# InternetButtonBuzzer.net
KiCad netlist of a schematic drawn in EAGLE
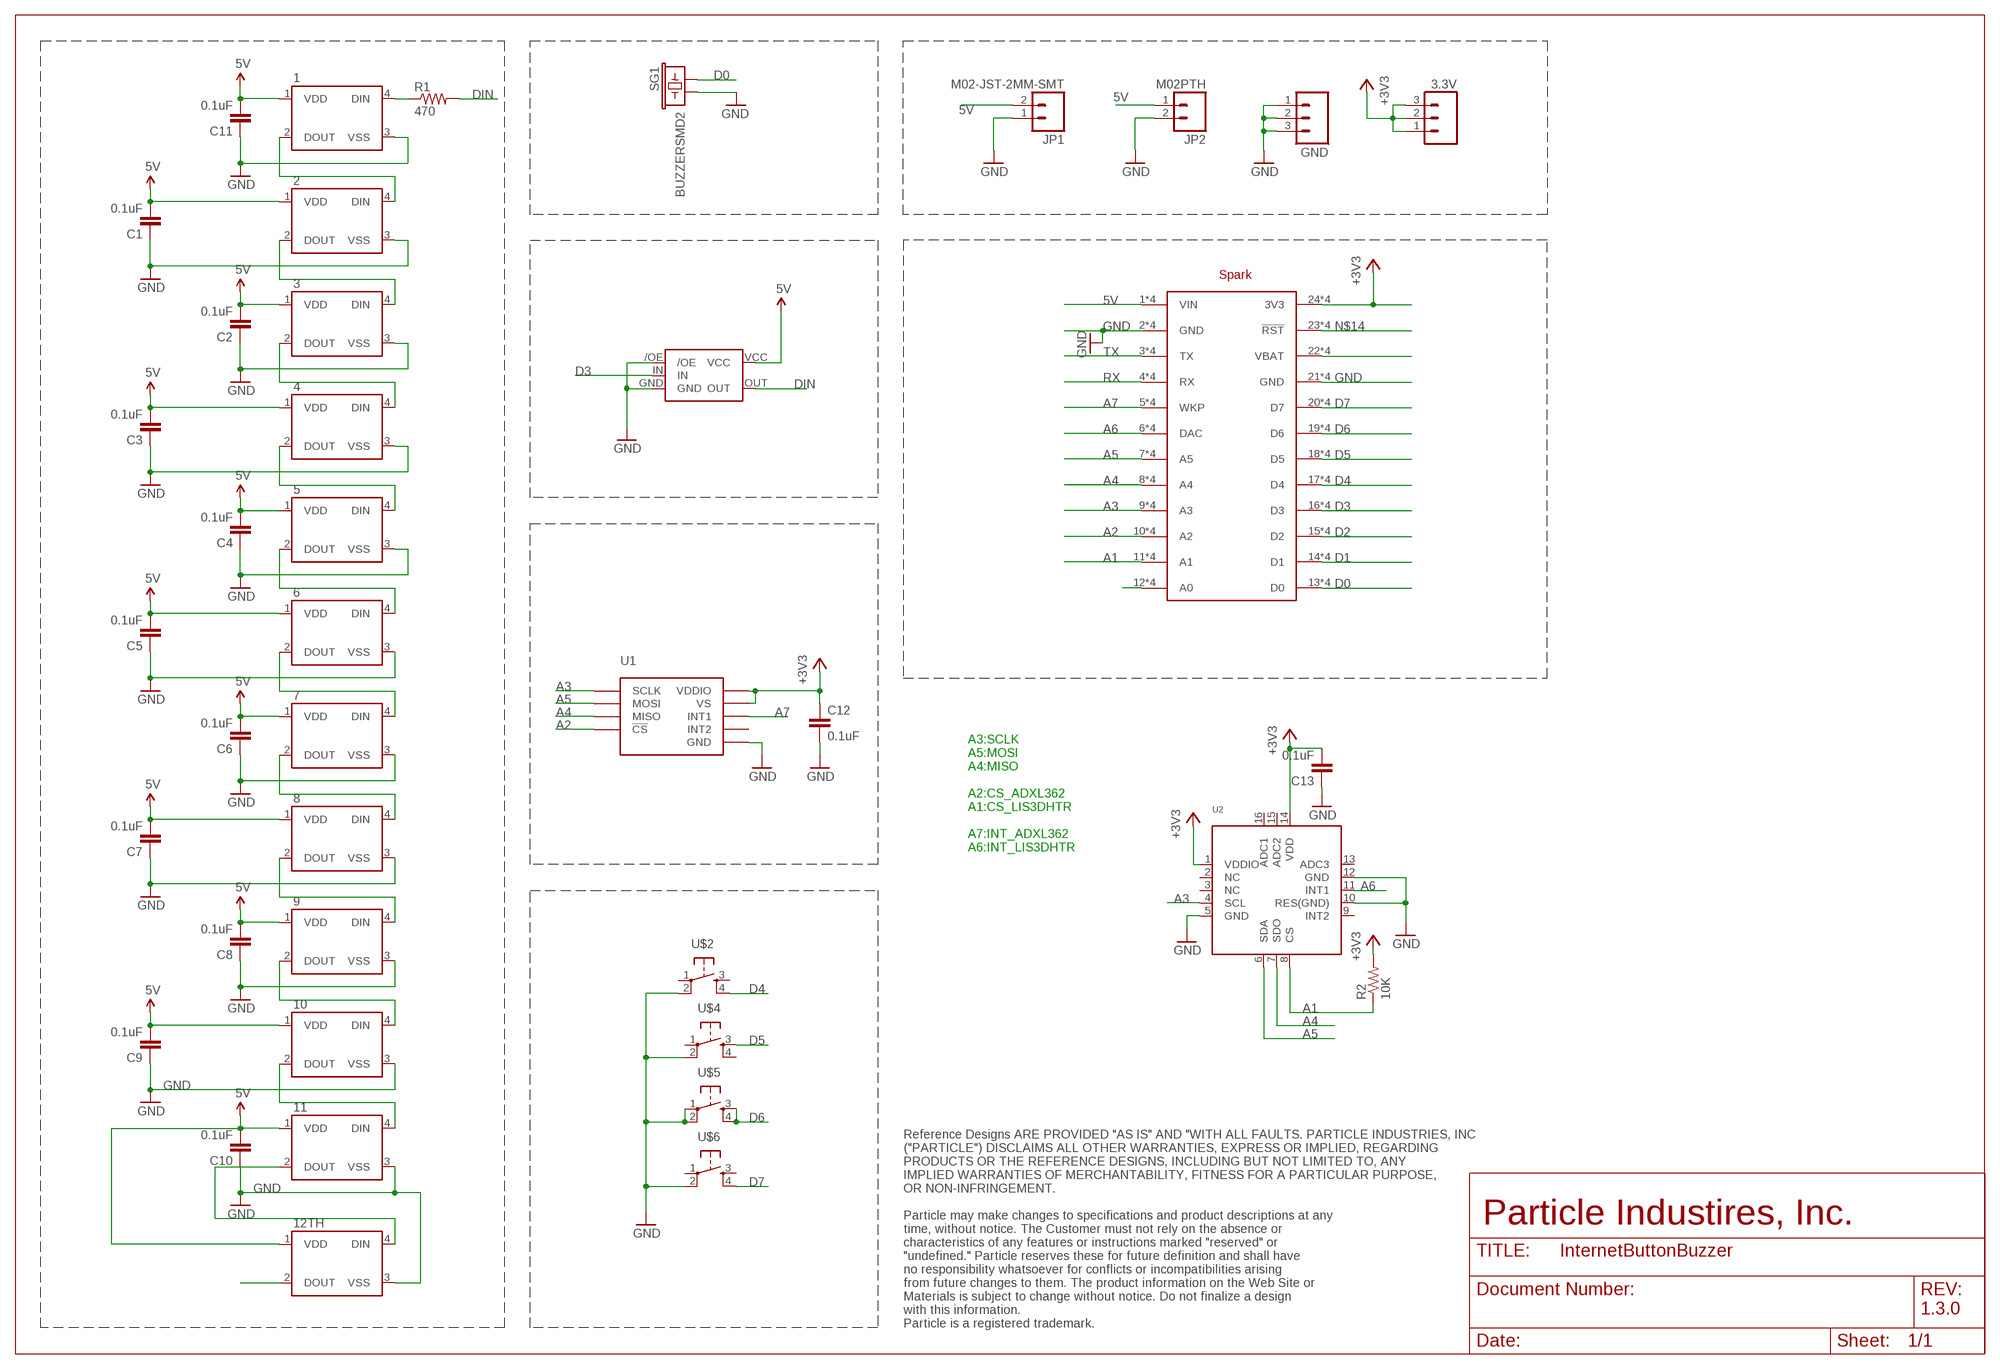
[diagram p0: schematic, sheet 1]

(export (version "E")
  (design (tool "Eeschema 10.0.6"))
  (components
    (comp (ref "1")
      (value "WS2812B")
      (footprint "eagle-import:WS2812B")
      (libsource (lib "eagle-import") (part "SparkFun-LED_WS2812B"))
    )
    (comp (ref "2")
      (value "WS2812B")
      (footprint "eagle-import:WS2812B")
      (libsource (lib "eagle-import") (part "SparkFun-LED_WS2812B"))
    )
    (comp (ref "3")
      (value "WS2812B")
      (footprint "eagle-import:WS2812B")
      (libsource (lib "eagle-import") (part "SparkFun-LED_WS2812B"))
    )
    (comp (ref "3.3V")
      (value "M03LOCK_NO_SILK")
      (footprint "eagle-import:1X03_LOCK_NO_SILK")
      (libsource (lib "eagle-import") (part "M03LOCK_NO_SILK"))
    )
    (comp (ref "4")
      (value "WS2812B")
      (footprint "eagle-import:WS2812B")
      (libsource (lib "eagle-import") (part "SparkFun-LED_WS2812B"))
    )
    (comp (ref "5")
      (value "WS2812B")
      (footprint "eagle-import:WS2812B")
      (libsource (lib "eagle-import") (part "SparkFun-LED_WS2812B"))
    )
    (comp (ref "6")
      (value "WS2812B")
      (footprint "eagle-import:WS2812B")
      (libsource (lib "eagle-import") (part "SparkFun-LED_WS2812B"))
    )
    (comp (ref "7")
      (value "WS2812B")
      (footprint "eagle-import:WS2812B")
      (libsource (lib "eagle-import") (part "SparkFun-LED_WS2812B"))
    )
    (comp (ref "8")
      (value "WS2812B")
      (footprint "eagle-import:WS2812B")
      (libsource (lib "eagle-import") (part "SparkFun-LED_WS2812B"))
    )
    (comp (ref "9")
      (value "WS2812B")
      (footprint "eagle-import:WS2812B")
      (libsource (lib "eagle-import") (part "SparkFun-LED_WS2812B"))
    )
    (comp (ref "10")
      (value "WS2812B")
      (footprint "eagle-import:WS2812B")
      (libsource (lib "eagle-import") (part "SparkFun-LED_WS2812B"))
    )
    (comp (ref "11")
      (value "WS2812B")
      (footprint "eagle-import:WS2812B")
      (libsource (lib "eagle-import") (part "SparkFun-LED_WS2812B"))
    )
    (comp (ref "12TH")
      (value "WS2812B")
      (footprint "eagle-import:NOCREAM_WS2812B")
      (libsource (lib "eagle-import") (part "WS2812B"))
    )
    (comp (ref "C1")
      (value "0.1uF")
      (footprint "eagle-import:0603-CAP")
      (libsource (lib "eagle-import") (part "15PF-50V-5%(0603)"))
    )
    (comp (ref "C2")
      (value "0.1uF")
      (footprint "eagle-import:0603-CAP")
      (libsource (lib "eagle-import") (part "15PF-50V-5%(0603)"))
    )
    (comp (ref "C3")
      (value "0.1uF")
      (footprint "eagle-import:0603-CAP")
      (libsource (lib "eagle-import") (part "15PF-50V-5%(0603)"))
    )
    (comp (ref "C4")
      (value "0.1uF")
      (footprint "eagle-import:0603-CAP")
      (libsource (lib "eagle-import") (part "15PF-50V-5%(0603)"))
    )
    (comp (ref "C5")
      (value "0.1uF")
      (footprint "eagle-import:0603-CAP")
      (libsource (lib "eagle-import") (part "15PF-50V-5%(0603)"))
    )
    (comp (ref "C6")
      (value "0.1uF")
      (footprint "eagle-import:0603-CAP")
      (libsource (lib "eagle-import") (part "15PF-50V-5%(0603)"))
    )
    (comp (ref "C7")
      (value "0.1uF")
      (footprint "eagle-import:0603-CAP")
      (libsource (lib "eagle-import") (part "15PF-50V-5%(0603)"))
    )
    (comp (ref "C8")
      (value "0.1uF")
      (footprint "eagle-import:0603-CAP")
      (libsource (lib "eagle-import") (part "15PF-50V-5%(0603)"))
    )
    (comp (ref "C9")
      (value "0.1uF")
      (footprint "eagle-import:0603-CAP")
      (libsource (lib "eagle-import") (part "15PF-50V-5%(0603)"))
    )
    (comp (ref "C10")
      (value "0.1uF")
      (footprint "eagle-import:0603-CAP")
      (libsource (lib "eagle-import") (part "15PF-50V-5%(0603)"))
    )
    (comp (ref "C11")
      (value "0.1uF")
      (footprint "eagle-import:0603-CAP")
      (libsource (lib "eagle-import") (part "15PF-50V-5%(0603)"))
    )
    (comp (ref "C12")
      (value "0.1uF")
      (footprint "eagle-import:0603-CAP")
      (libsource (lib "eagle-import") (part "CAP0603-CAP"))
    )
    (comp (ref "C13")
      (value "0.1uF")
      (footprint "eagle-import:0603-CAP")
      (libsource (lib "eagle-import") (part "CAP0603-CAP"))
    )
    (comp (ref "GND")
      (value "M03LOCK_NO_SILK")
      (footprint "eagle-import:1X03_LOCK_NO_SILK")
      (libsource (lib "eagle-import") (part "M03LOCK_NO_SILK"))
    )
    (comp (ref "JP1")
      (value "M02-JST-2MM-SMT")
      (footprint "eagle-import:JST-2-SMD")
      (libsource (lib "eagle-import") (part "M02-JST-2MM-SMT"))
    )
    (comp (ref "JP2")
      (value "M02PTH")
      (footprint "eagle-import:1X02")
      (libsource (lib "eagle-import") (part "M02PTH"))
    )
    (comp (ref "R1")
      (value "470")
      (footprint "eagle-import:0603-RES")
      (libsource (lib "eagle-import") (part "470OHM1/10W1%(0603)"))
    )
    (comp (ref "R2")
      (value "10K")
      (footprint "eagle-import:0603-RES")
      (libsource (lib "eagle-import") (part "470OHM1/10W1%(0603)"))
    )
    (comp (ref "SG1")
      (value "BUZZERSMD2")
      (footprint "eagle-import:BUZZER-CCV")
      (libsource (lib "eagle-import") (part "BUZZERSMD2"))
    )
    (comp (ref "U$2")
      (value "12MM_TACTILE_SWITCH")
      (footprint "eagle-import:12MM_TACTILE_SWITCH")
      (libsource (lib "eagle-import") (part "12MM_TACTILE_SWITCH"))
    )
    (comp (ref "U$3")
      (value "SPARK_LOGO_WITH_PLANE")
      (footprint "eagle-import:SPARK_LOGO_PLUS_PLANE")
      (libsource (lib "eagle-import") (part "SPARK_LOGO_WITH_PLANE"))
    )
    (comp (ref "U$4")
      (value "12MM_TACTILE_SWITCH")
      (footprint "eagle-import:12MM_TACTILE_SWITCH")
      (libsource (lib "eagle-import") (part "12MM_TACTILE_SWITCH"))
    )
    (comp (ref "U$5")
      (value "12MM_TACTILE_SWITCH")
      (footprint "eagle-import:12MM_TACTILE_SWITCH")
      (libsource (lib "eagle-import") (part "12MM_TACTILE_SWITCH"))
    )
    (comp (ref "U$6")
      (value "12MM_TACTILE_SWITCH")
      (footprint "eagle-import:12MM_TACTILE_SWITCH")
      (libsource (lib "eagle-import") (part "12MM_TACTILE_SWITCH"))
    )
    (comp (ref "U$7")
      (value "SPARK_COREDUAL_HEADER")
      (footprint "eagle-import:SPARK_CORE_DUAL_HEADER")
      (libsource (lib "eagle-import") (part "SPARK_COREDUAL_HEADER"))
    )
    (comp (ref "U$8")
      (value "NL17SZ125SOT553")
      (footprint "eagle-import:SOT-553")
      (libsource (lib "eagle-import") (part "NL17SZ125SOT553"))
    )
    (comp (ref "U1")
      (value "ADXL362ADXL362-1:1")
      (footprint "eagle-import:ADXL362-1_1")
      (libsource (lib "eagle-import") (part "ADXL362ADXL362-1{colon}1"))
    )
    (comp (ref "U2")
      (value "ACCEL_LIS3DHTR")
      (footprint "eagle-import:LGA16_3X3MM")
      (libsource (lib "eagle-import") (part "ACCEL_LIS3DHTR"))
    )
  )
  (nets
    (net (code "1") (name "+3V3") (class "Default")
      (node (ref "3.3V") (pin "1") (pinfunction "1_1") (pintype "passive"))
      (node (ref "3.3V") (pin "2") (pinfunction "2_2") (pintype "passive"))
      (node (ref "3.3V") (pin "3") (pinfunction "3_3") (pintype "passive"))
      (node (ref "C12") (pin "1") (pinfunction "1_1") (pintype "passive"))
      (node (ref "C13") (pin "2") (pinfunction "2_2") (pintype "passive"))
      (node (ref "R2") (pin "2") (pinfunction "2_2") (pintype "passive"))
      (node (ref "U$7") (pin "24") (pinfunction "3V3_24") (pintype "power_in"))
      (node (ref "U$7") (pin "24B") (pinfunction "3V3_24B") (pintype "power_in"))
      (node (ref "U$7") (pin "@24") (pinfunction "3V3_@24") (pintype "power_in"))
      (node (ref "U$7") (pin "@24B") (pinfunction "3V3_@24B") (pintype "power_in"))
      (node (ref "U1") (pin "P$1") (pinfunction "VDDIO_P$1") (pintype "bidirectional"))
      (node (ref "U1") (pin "P$14") (pinfunction "VS_P$14") (pintype "bidirectional"))
      (node (ref "U2") (pin "1") (pinfunction "VDDIO_1") (pintype "power_in"))
      (node (ref "U2") (pin "14") (pinfunction "VDD_14") (pintype "power_in"))
    )
    (net (code "2") (name "/A1") (class "Default")
      (node (ref "R2") (pin "1") (pinfunction "1_1") (pintype "passive"))
      (node (ref "U$7") (pin "11") (pinfunction "A1_11") (pintype "bidirectional"))
      (node (ref "U$7") (pin "11B") (pinfunction "A1_11B") (pintype "bidirectional"))
      (node (ref "U$7") (pin "@11") (pinfunction "A1_@11") (pintype "bidirectional"))
      (node (ref "U$7") (pin "@11B") (pinfunction "A1_@11B") (pintype "bidirectional"))
      (node (ref "U2") (pin "8") (pinfunction "CS_8") (pintype "input"))
    )
    (net (code "3") (name "/A2") (class "Default")
      (node (ref "U$7") (pin "10") (pinfunction "A2_10") (pintype "bidirectional"))
      (node (ref "U$7") (pin "10B") (pinfunction "A2_10B") (pintype "bidirectional"))
      (node (ref "U$7") (pin "@10") (pinfunction "A2_@10") (pintype "bidirectional"))
      (node (ref "U$7") (pin "@10B") (pinfunction "A2_@10B") (pintype "bidirectional"))
      (node (ref "U1") (pin "P$8") (pinfunction "~{CS}_P$8") (pintype "bidirectional"))
    )
    (net (code "4") (name "/A3") (class "Default")
      (node (ref "U$7") (pin "9") (pinfunction "A3_9") (pintype "bidirectional"))
      (node (ref "U$7") (pin "9B") (pinfunction "A3_9B") (pintype "bidirectional"))
      (node (ref "U$7") (pin "@9") (pinfunction "A3_@9") (pintype "bidirectional"))
      (node (ref "U$7") (pin "@9B") (pinfunction "A3_@9B") (pintype "bidirectional"))
      (node (ref "U1") (pin "P$4") (pinfunction "SCLK_P$4") (pintype "bidirectional"))
      (node (ref "U2") (pin "4") (pinfunction "SCL_4") (pintype "bidirectional"))
    )
    (net (code "5") (name "/A4") (class "Default")
      (node (ref "U$7") (pin "8") (pinfunction "A4_8") (pintype "bidirectional"))
      (node (ref "U$7") (pin "8B") (pinfunction "A4_8B") (pintype "bidirectional"))
      (node (ref "U$7") (pin "@8") (pinfunction "A4_@8") (pintype "bidirectional"))
      (node (ref "U$7") (pin "@8B") (pinfunction "A4_@8B") (pintype "bidirectional"))
      (node (ref "U1") (pin "P$7") (pinfunction "MISO_P$7") (pintype "bidirectional"))
      (node (ref "U2") (pin "7") (pinfunction "SDO_7") (pintype "bidirectional"))
    )
    (net (code "6") (name "/A5") (class "Default")
      (node (ref "U$7") (pin "7") (pinfunction "A5_7") (pintype "bidirectional"))
      (node (ref "U$7") (pin "7B") (pinfunction "A5_7B") (pintype "bidirectional"))
      (node (ref "U$7") (pin "@7") (pinfunction "A5_@7") (pintype "bidirectional"))
      (node (ref "U$7") (pin "@7B") (pinfunction "A5_@7B") (pintype "bidirectional"))
      (node (ref "U1") (pin "P$6") (pinfunction "MOSI_P$6") (pintype "bidirectional"))
      (node (ref "U2") (pin "6") (pinfunction "SDA_6") (pintype "bidirectional"))
    )
    (net (code "7") (name "/A6") (class "Default")
      (node (ref "U$7") (pin "6") (pinfunction "DAC_6") (pintype "bidirectional"))
      (node (ref "U$7") (pin "6B") (pinfunction "DAC_6B") (pintype "bidirectional"))
      (node (ref "U$7") (pin "@6") (pinfunction "DAC_@6") (pintype "bidirectional"))
      (node (ref "U$7") (pin "@6B") (pinfunction "DAC_@6B") (pintype "bidirectional"))
      (node (ref "U2") (pin "11") (pinfunction "INT1_11") (pintype "output"))
    )
    (net (code "8") (name "/A7") (class "Default")
      (node (ref "U$7") (pin "5") (pinfunction "WKP_5") (pintype "bidirectional"))
      (node (ref "U$7") (pin "5B") (pinfunction "WKP_5B") (pintype "bidirectional"))
      (node (ref "U$7") (pin "@5") (pinfunction "WKP_@5") (pintype "bidirectional"))
      (node (ref "U$7") (pin "@5B") (pinfunction "WKP_@5B") (pintype "bidirectional"))
      (node (ref "U1") (pin "P$11") (pinfunction "INT1_P$11") (pintype "bidirectional"))
    )
    (net (code "9") (name "/D0") (class "Default")
      (node (ref "SG1") (pin "+") (pinfunction "1_+") (pintype "passive"))
      (node (ref "U$7") (pin "13") (pinfunction "D0_13") (pintype "bidirectional"))
      (node (ref "U$7") (pin "13B") (pinfunction "D0_13B") (pintype "bidirectional"))
      (node (ref "U$7") (pin "@13") (pinfunction "D0_@13") (pintype "bidirectional"))
      (node (ref "U$7") (pin "@13B") (pinfunction "D0_@13B") (pintype "bidirectional"))
    )
    (net (code "10") (name "/D1") (class "Default")
      (node (ref "U$7") (pin "14") (pinfunction "D1_14") (pintype "bidirectional"))
      (node (ref "U$7") (pin "14B") (pinfunction "D1_14B") (pintype "bidirectional"))
      (node (ref "U$7") (pin "@14") (pinfunction "D1_@14") (pintype "bidirectional"))
      (node (ref "U$7") (pin "@14B") (pinfunction "D1_@14B") (pintype "bidirectional"))
    )
    (net (code "11") (name "/D2") (class "Default")
      (node (ref "U$7") (pin "15") (pinfunction "D2_15") (pintype "bidirectional"))
      (node (ref "U$7") (pin "15B") (pinfunction "D2_15B") (pintype "bidirectional"))
      (node (ref "U$7") (pin "@15") (pinfunction "D2_@15") (pintype "bidirectional"))
      (node (ref "U$7") (pin "@15B") (pinfunction "D2_@15B") (pintype "bidirectional"))
    )
    (net (code "12") (name "/D3") (class "Default")
      (node (ref "U$7") (pin "16") (pinfunction "D3_16") (pintype "bidirectional"))
      (node (ref "U$7") (pin "16B") (pinfunction "D3_16B") (pintype "bidirectional"))
      (node (ref "U$7") (pin "@16") (pinfunction "D3_@16") (pintype "bidirectional"))
      (node (ref "U$7") (pin "@16B") (pinfunction "D3_@16B") (pintype "bidirectional"))
      (node (ref "U$8") (pin "IN") (pinfunction "IN_IN") (pintype "bidirectional"))
    )
    (net (code "13") (name "/D4") (class "Default")
      (node (ref "U$2") (pin "4") (pinfunction "4_4") (pintype "passive"))
      (node (ref "U$7") (pin "17") (pinfunction "D4_17") (pintype "bidirectional"))
      (node (ref "U$7") (pin "17B") (pinfunction "D4_17B") (pintype "bidirectional"))
      (node (ref "U$7") (pin "@17") (pinfunction "D4_@17") (pintype "bidirectional"))
      (node (ref "U$7") (pin "@17B") (pinfunction "D4_@17B") (pintype "bidirectional"))
    )
    (net (code "14") (name "/D5") (class "Default")
      (node (ref "U$4") (pin "3") (pinfunction "3_3") (pintype "passive"))
      (node (ref "U$7") (pin "18") (pinfunction "D5_18") (pintype "bidirectional"))
      (node (ref "U$7") (pin "18B") (pinfunction "D5_18B") (pintype "bidirectional"))
      (node (ref "U$7") (pin "@18") (pinfunction "D5_@18") (pintype "bidirectional"))
      (node (ref "U$7") (pin "@18B") (pinfunction "D5_@18B") (pintype "bidirectional"))
    )
    (net (code "15") (name "/D6") (class "Default")
      (node (ref "U$5") (pin "3") (pinfunction "3_3") (pintype "passive"))
      (node (ref "U$5") (pin "4") (pinfunction "4_4") (pintype "passive"))
      (node (ref "U$7") (pin "19") (pinfunction "D6_19") (pintype "bidirectional"))
      (node (ref "U$7") (pin "19B") (pinfunction "D6_19B") (pintype "bidirectional"))
      (node (ref "U$7") (pin "@19") (pinfunction "D6_@19") (pintype "bidirectional"))
      (node (ref "U$7") (pin "@19B") (pinfunction "D6_@19B") (pintype "bidirectional"))
    )
    (net (code "16") (name "/D7") (class "Default")
      (node (ref "U$6") (pin "4") (pinfunction "4_4") (pintype "passive"))
      (node (ref "U$7") (pin "20") (pinfunction "D7_20") (pintype "bidirectional"))
      (node (ref "U$7") (pin "20B") (pinfunction "D7_20B") (pintype "bidirectional"))
      (node (ref "U$7") (pin "@20") (pinfunction "D7_@20") (pintype "bidirectional"))
      (node (ref "U$7") (pin "@20B") (pinfunction "D7_@20B") (pintype "bidirectional"))
    )
    (net (code "17") (name "/DIN") (class "Default")
      (node (ref "R1") (pin "2") (pinfunction "2_2") (pintype "passive"))
      (node (ref "U$8") (pin "OUT") (pinfunction "OUT_OUT") (pintype "bidirectional"))
    )
    (net (code "18") (name "/N$14") (class "Default")
      (node (ref "U$7") (pin "23") (pinfunction "~{RST}_23") (pintype "bidirectional"))
      (node (ref "U$7") (pin "23B") (pinfunction "~{RST}_23B") (pintype "bidirectional"))
      (node (ref "U$7") (pin "@23") (pinfunction "~{RST}_@23") (pintype "bidirectional"))
      (node (ref "U$7") (pin "@23B") (pinfunction "~{RST}_@23B") (pintype "bidirectional"))
    )
    (net (code "19") (name "/RX") (class "Default")
      (node (ref "U$7") (pin "4") (pinfunction "RX_4") (pintype "bidirectional"))
      (node (ref "U$7") (pin "4B") (pinfunction "RX_4B") (pintype "bidirectional"))
      (node (ref "U$7") (pin "@4") (pinfunction "RX_@4") (pintype "bidirectional"))
      (node (ref "U$7") (pin "@4B") (pinfunction "RX_@4B") (pintype "bidirectional"))
    )
    (net (code "20") (name "/TX") (class "Default")
      (node (ref "U$7") (pin "3") (pinfunction "TX_3") (pintype "bidirectional"))
      (node (ref "U$7") (pin "3B") (pinfunction "TX_3B") (pintype "bidirectional"))
      (node (ref "U$7") (pin "@3") (pinfunction "TX_@3") (pintype "bidirectional"))
      (node (ref "U$7") (pin "@3B") (pinfunction "TX_@3B") (pintype "bidirectional"))
    )
    (net (code "21") (name "5V") (class "Default")
      (node (ref "1") (pin "1") (pinfunction "VDD_1") (pintype "power_in"))
      (node (ref "10") (pin "1") (pinfunction "VDD_1") (pintype "power_in"))
      (node (ref "11") (pin "1") (pinfunction "VDD_1") (pintype "power_in"))
      (node (ref "12TH") (pin "1") (pinfunction "VDD_1") (pintype "power_in"))
      (node (ref "2") (pin "1") (pinfunction "VDD_1") (pintype "power_in"))
      (node (ref "3") (pin "1") (pinfunction "VDD_1") (pintype "power_in"))
      (node (ref "4") (pin "1") (pinfunction "VDD_1") (pintype "power_in"))
      (node (ref "5") (pin "1") (pinfunction "VDD_1") (pintype "power_in"))
      (node (ref "6") (pin "1") (pinfunction "VDD_1") (pintype "power_in"))
      (node (ref "7") (pin "1") (pinfunction "VDD_1") (pintype "power_in"))
      (node (ref "8") (pin "1") (pinfunction "VDD_1") (pintype "power_in"))
      (node (ref "9") (pin "1") (pinfunction "VDD_1") (pintype "power_in"))
      (node (ref "C1") (pin "2") (pinfunction "2_2") (pintype "passive"))
      (node (ref "C10") (pin "2") (pinfunction "2_2") (pintype "passive"))
      (node (ref "C11") (pin "2") (pinfunction "2_2") (pintype "passive"))
      (node (ref "C2") (pin "2") (pinfunction "2_2") (pintype "passive"))
      (node (ref "C3") (pin "2") (pinfunction "2_2") (pintype "passive"))
      (node (ref "C4") (pin "2") (pinfunction "2_2") (pintype "passive"))
      (node (ref "C5") (pin "2") (pinfunction "2_2") (pintype "passive"))
      (node (ref "C6") (pin "2") (pinfunction "2_2") (pintype "passive"))
      (node (ref "C7") (pin "2") (pinfunction "2_2") (pintype "passive"))
      (node (ref "C8") (pin "2") (pinfunction "2_2") (pintype "passive"))
      (node (ref "C9") (pin "2") (pinfunction "2_2") (pintype "passive"))
      (node (ref "JP1") (pin "2") (pinfunction "1_2") (pintype "passive"))
      (node (ref "JP2") (pin "1") (pinfunction "1_1") (pintype "passive"))
      (node (ref "U$7") (pin "1") (pinfunction "VIN_1") (pintype "power_in"))
      (node (ref "U$7") (pin "1B") (pinfunction "VIN_1B") (pintype "power_in"))
      (node (ref "U$7") (pin "@1") (pinfunction "VIN_@1") (pintype "power_in"))
      (node (ref "U$7") (pin "@1B") (pinfunction "VIN_@1B") (pintype "power_in"))
      (node (ref "U$8") (pin "VCC") (pinfunction "VCC_VCC") (pintype "bidirectional"))
    )
    (net (code "22") (name "GND") (class "Default")
      (node (ref "1") (pin "3") (pinfunction "VSS_3") (pintype "power_in"))
      (node (ref "10") (pin "3") (pinfunction "VSS_3") (pintype "power_in"))
      (node (ref "11") (pin "3") (pinfunction "VSS_3") (pintype "power_in"))
      (node (ref "12TH") (pin "3") (pinfunction "VSS_3") (pintype "power_in"))
      (node (ref "2") (pin "3") (pinfunction "VSS_3") (pintype "power_in"))
      (node (ref "3") (pin "3") (pinfunction "VSS_3") (pintype "power_in"))
      (node (ref "4") (pin "3") (pinfunction "VSS_3") (pintype "power_in"))
      (node (ref "5") (pin "3") (pinfunction "VSS_3") (pintype "power_in"))
      (node (ref "6") (pin "3") (pinfunction "VSS_3") (pintype "power_in"))
      (node (ref "7") (pin "3") (pinfunction "VSS_3") (pintype "power_in"))
      (node (ref "8") (pin "3") (pinfunction "VSS_3") (pintype "power_in"))
      (node (ref "9") (pin "3") (pinfunction "VSS_3") (pintype "power_in"))
      (node (ref "C1") (pin "1") (pinfunction "1_1") (pintype "passive"))
      (node (ref "C10") (pin "1") (pinfunction "1_1") (pintype "passive"))
      (node (ref "C11") (pin "1") (pinfunction "1_1") (pintype "passive"))
      (node (ref "C12") (pin "2") (pinfunction "2_2") (pintype "passive"))
      (node (ref "C13") (pin "1") (pinfunction "1_1") (pintype "passive"))
      (node (ref "C2") (pin "1") (pinfunction "1_1") (pintype "passive"))
      (node (ref "C3") (pin "1") (pinfunction "1_1") (pintype "passive"))
      (node (ref "C4") (pin "1") (pinfunction "1_1") (pintype "passive"))
      (node (ref "C5") (pin "1") (pinfunction "1_1") (pintype "passive"))
      (node (ref "C6") (pin "1") (pinfunction "1_1") (pintype "passive"))
      (node (ref "C7") (pin "1") (pinfunction "1_1") (pintype "passive"))
      (node (ref "C8") (pin "1") (pinfunction "1_1") (pintype "passive"))
      (node (ref "C9") (pin "1") (pinfunction "1_1") (pintype "passive"))
      (node (ref "GND") (pin "1") (pinfunction "1_1") (pintype "passive"))
      (node (ref "GND") (pin "2") (pinfunction "2_2") (pintype "passive"))
      (node (ref "GND") (pin "3") (pinfunction "3_3") (pintype "passive"))
      (node (ref "JP1") (pin "1") (pinfunction "2_1") (pintype "passive"))
      (node (ref "JP2") (pin "2") (pinfunction "2_2") (pintype "passive"))
      (node (ref "SG1") (pin "-") (pinfunction "2_-") (pintype "passive"))
      (node (ref "U$2") (pin "2") (pinfunction "2_2") (pintype "passive"))
      (node (ref "U$4") (pin "2") (pinfunction "2_2") (pintype "passive"))
      (node (ref "U$5") (pin "1") (pinfunction "1_1") (pintype "passive"))
      (node (ref "U$5") (pin "2") (pinfunction "2_2") (pintype "passive"))
      (node (ref "U$6") (pin "2") (pinfunction "2_2") (pintype "passive"))
      (node (ref "U$7") (pin "2") (pinfunction "GND_2") (pintype "power_in"))
      (node (ref "U$7") (pin "21") (pinfunction "GND_21") (pintype "power_in"))
      (node (ref "U$7") (pin "21B") (pinfunction "GND_21B") (pintype "power_in"))
      (node (ref "U$7") (pin "2B") (pinfunction "GND_2B") (pintype "power_in"))
      (node (ref "U$7") (pin "@2") (pinfunction "GND_@2") (pintype "power_in"))
      (node (ref "U$7") (pin "@21") (pinfunction "GND_@21") (pintype "power_in"))
      (node (ref "U$7") (pin "@21B") (pinfunction "GND_@21B") (pintype "power_in"))
      (node (ref "U$7") (pin "@2B") (pinfunction "GND_@2B") (pintype "power_in"))
      (node (ref "U$8") (pin "/OE") (pinfunction "/OE_/OE") (pintype "bidirectional"))
      (node (ref "U$8") (pin "GND") (pinfunction "GND_GND") (pintype "bidirectional"))
      (node (ref "U1") (pin "P$12") (pinfunction "GND_P$12") (pintype "bidirectional"))
      (node (ref "U1") (pin "P$13") (pinfunction "GND_P$13") (pintype "bidirectional"))
      (node (ref "U1") (pin "P$16") (pinfunction "GND_P$16") (pintype "bidirectional"))
      (node (ref "U2") (pin "10") (pinfunction "RES(GND)_10") (pintype "bidirectional"))
      (node (ref "U2") (pin "12") (pinfunction "GND_12") (pintype "power_in"))
      (node (ref "U2") (pin "5") (pinfunction "GND_5") (pintype "power_in"))
    )
    (net (code "23") (name "Net-(1-DIN)") (class "Default")
      (node (ref "1") (pin "4") (pinfunction "DIN_4") (pintype "input"))
      (node (ref "R1") (pin "1") (pinfunction "1_1") (pintype "passive"))
    )
    (net (code "24") (name "Net-(1-DOUT)") (class "Default")
      (node (ref "1") (pin "2") (pinfunction "DOUT_2") (pintype "output"))
      (node (ref "2") (pin "4") (pinfunction "DIN_4") (pintype "input"))
    )
    (net (code "25") (name "Net-(2-DOUT)") (class "Default")
      (node (ref "2") (pin "2") (pinfunction "DOUT_2") (pintype "output"))
      (node (ref "3") (pin "4") (pinfunction "DIN_4") (pintype "input"))
    )
    (net (code "26") (name "Net-(3-DOUT)") (class "Default")
      (node (ref "3") (pin "2") (pinfunction "DOUT_2") (pintype "output"))
      (node (ref "4") (pin "4") (pinfunction "DIN_4") (pintype "input"))
    )
    (net (code "27") (name "Net-(4-DOUT)") (class "Default")
      (node (ref "4") (pin "2") (pinfunction "DOUT_2") (pintype "output"))
      (node (ref "5") (pin "4") (pinfunction "DIN_4") (pintype "input"))
    )
    (net (code "28") (name "Net-(5-DOUT)") (class "Default")
      (node (ref "5") (pin "2") (pinfunction "DOUT_2") (pintype "output"))
      (node (ref "6") (pin "4") (pinfunction "DIN_4") (pintype "input"))
    )
    (net (code "29") (name "Net-(6-DOUT)") (class "Default")
      (node (ref "6") (pin "2") (pinfunction "DOUT_2") (pintype "output"))
      (node (ref "7") (pin "4") (pinfunction "DIN_4") (pintype "input"))
    )
    (net (code "30") (name "Net-(7-DOUT)") (class "Default")
      (node (ref "7") (pin "2") (pinfunction "DOUT_2") (pintype "output"))
      (node (ref "8") (pin "4") (pinfunction "DIN_4") (pintype "input"))
    )
    (net (code "31") (name "Net-(8-DOUT)") (class "Default")
      (node (ref "8") (pin "2") (pinfunction "DOUT_2") (pintype "output"))
      (node (ref "9") (pin "4") (pinfunction "DIN_4") (pintype "input"))
    )
    (net (code "32") (name "Net-(10-DIN)") (class "Default")
      (node (ref "10") (pin "4") (pinfunction "DIN_4") (pintype "input"))
      (node (ref "9") (pin "2") (pinfunction "DOUT_2") (pintype "output"))
    )
    (net (code "33") (name "Net-(10-DOUT)") (class "Default")
      (node (ref "10") (pin "2") (pinfunction "DOUT_2") (pintype "output"))
      (node (ref "11") (pin "4") (pinfunction "DIN_4") (pintype "input"))
    )
    (net (code "34") (name "Net-(11-DOUT)") (class "Default")
      (node (ref "11") (pin "2") (pinfunction "DOUT_2") (pintype "output"))
      (node (ref "12TH") (pin "4") (pinfunction "DIN_4") (pintype "input"))
    )
    (net (code "35") (name "Net-(U$7-A0-Pad12)") (class "Default")
      (node (ref "U$7") (pin "12") (pinfunction "A0_12") (pintype "bidirectional"))
      (node (ref "U$7") (pin "12B") (pinfunction "A0_12B") (pintype "bidirectional"))
      (node (ref "U$7") (pin "@12") (pinfunction "A0_@12") (pintype "bidirectional"))
      (node (ref "U$7") (pin "@12B") (pinfunction "A0_@12B") (pintype "bidirectional"))
    )
    (net (code "36") (name "Net-(U$7-VBAT-Pad22)") (class "Default")
      (node (ref "U$7") (pin "22") (pinfunction "VBAT_22") (pintype "power_in"))
      (node (ref "U$7") (pin "22B") (pinfunction "VBAT_22B") (pintype "power_in"))
      (node (ref "U$7") (pin "@22") (pinfunction "VBAT_@22") (pintype "power_in"))
      (node (ref "U$7") (pin "@22B") (pinfunction "VBAT_@22B") (pintype "power_in"))
    )
    (net (code "37") (name "unconnected-(12TH-DOUT-Pad2)") (class "Default")
      (node (ref "12TH") (pin "2") (pinfunction "DOUT_2") (pintype "output"))
    )
    (net (code "38") (name "unconnected-(U$2-Pad1)") (class "Default")
      (node (ref "U$2") (pin "1") (pinfunction "1_1") (pintype "passive"))
    )
    (net (code "39") (name "unconnected-(U$2-Pad3)") (class "Default")
      (node (ref "U$2") (pin "3") (pinfunction "3_3") (pintype "passive"))
    )
    (net (code "40") (name "unconnected-(U$4-Pad1)") (class "Default")
      (node (ref "U$4") (pin "1") (pinfunction "1_1") (pintype "passive"))
    )
    (net (code "41") (name "unconnected-(U$4-Pad4)") (class "Default")
      (node (ref "U$4") (pin "4") (pinfunction "4_4") (pintype "passive"))
    )
    (net (code "42") (name "unconnected-(U$6-Pad1)") (class "Default")
      (node (ref "U$6") (pin "1") (pinfunction "1_1") (pintype "passive"))
    )
    (net (code "43") (name "unconnected-(U$6-Pad3)") (class "Default")
      (node (ref "U$6") (pin "3") (pinfunction "3_3") (pintype "passive"))
    )
    (net (code "44") (name "unconnected-(U1-INT2-PadP$9)") (class "Default")
      (node (ref "U1") (pin "P$9") (pinfunction "INT2_P$9") (pintype "bidirectional"))
    )
    (net (code "45") (name "unconnected-(U2-ADC1-Pad16)") (class "Default")
      (node (ref "U2") (pin "16") (pinfunction "ADC1_16") (pintype "input"))
    )
    (net (code "46") (name "unconnected-(U2-ADC2-Pad15)") (class "Default")
      (node (ref "U2") (pin "15") (pinfunction "ADC2_15") (pintype "input"))
    )
    (net (code "47") (name "unconnected-(U2-ADC3-Pad13)") (class "Default")
      (node (ref "U2") (pin "13") (pinfunction "ADC3_13") (pintype "input"))
    )
    (net (code "48") (name "unconnected-(U2-INT2-Pad9)") (class "Default")
      (node (ref "U2") (pin "9") (pinfunction "INT2_9") (pintype "output"))
    )
    (net (code "49") (name "unconnected-(U2-NC-Pad2)") (class "Default")
      (node (ref "U2") (pin "2") (pinfunction "NC_2") (pintype "no_connect"))
    )
    (net (code "50") (name "unconnected-(U2-NC-Pad3)") (class "Default")
      (node (ref "U2") (pin "3") (pinfunction "NC_3") (pintype "no_connect"))
    )
  )
)
